# Schematic.net
KiCad netlist of a schematic drawn in EAGLE
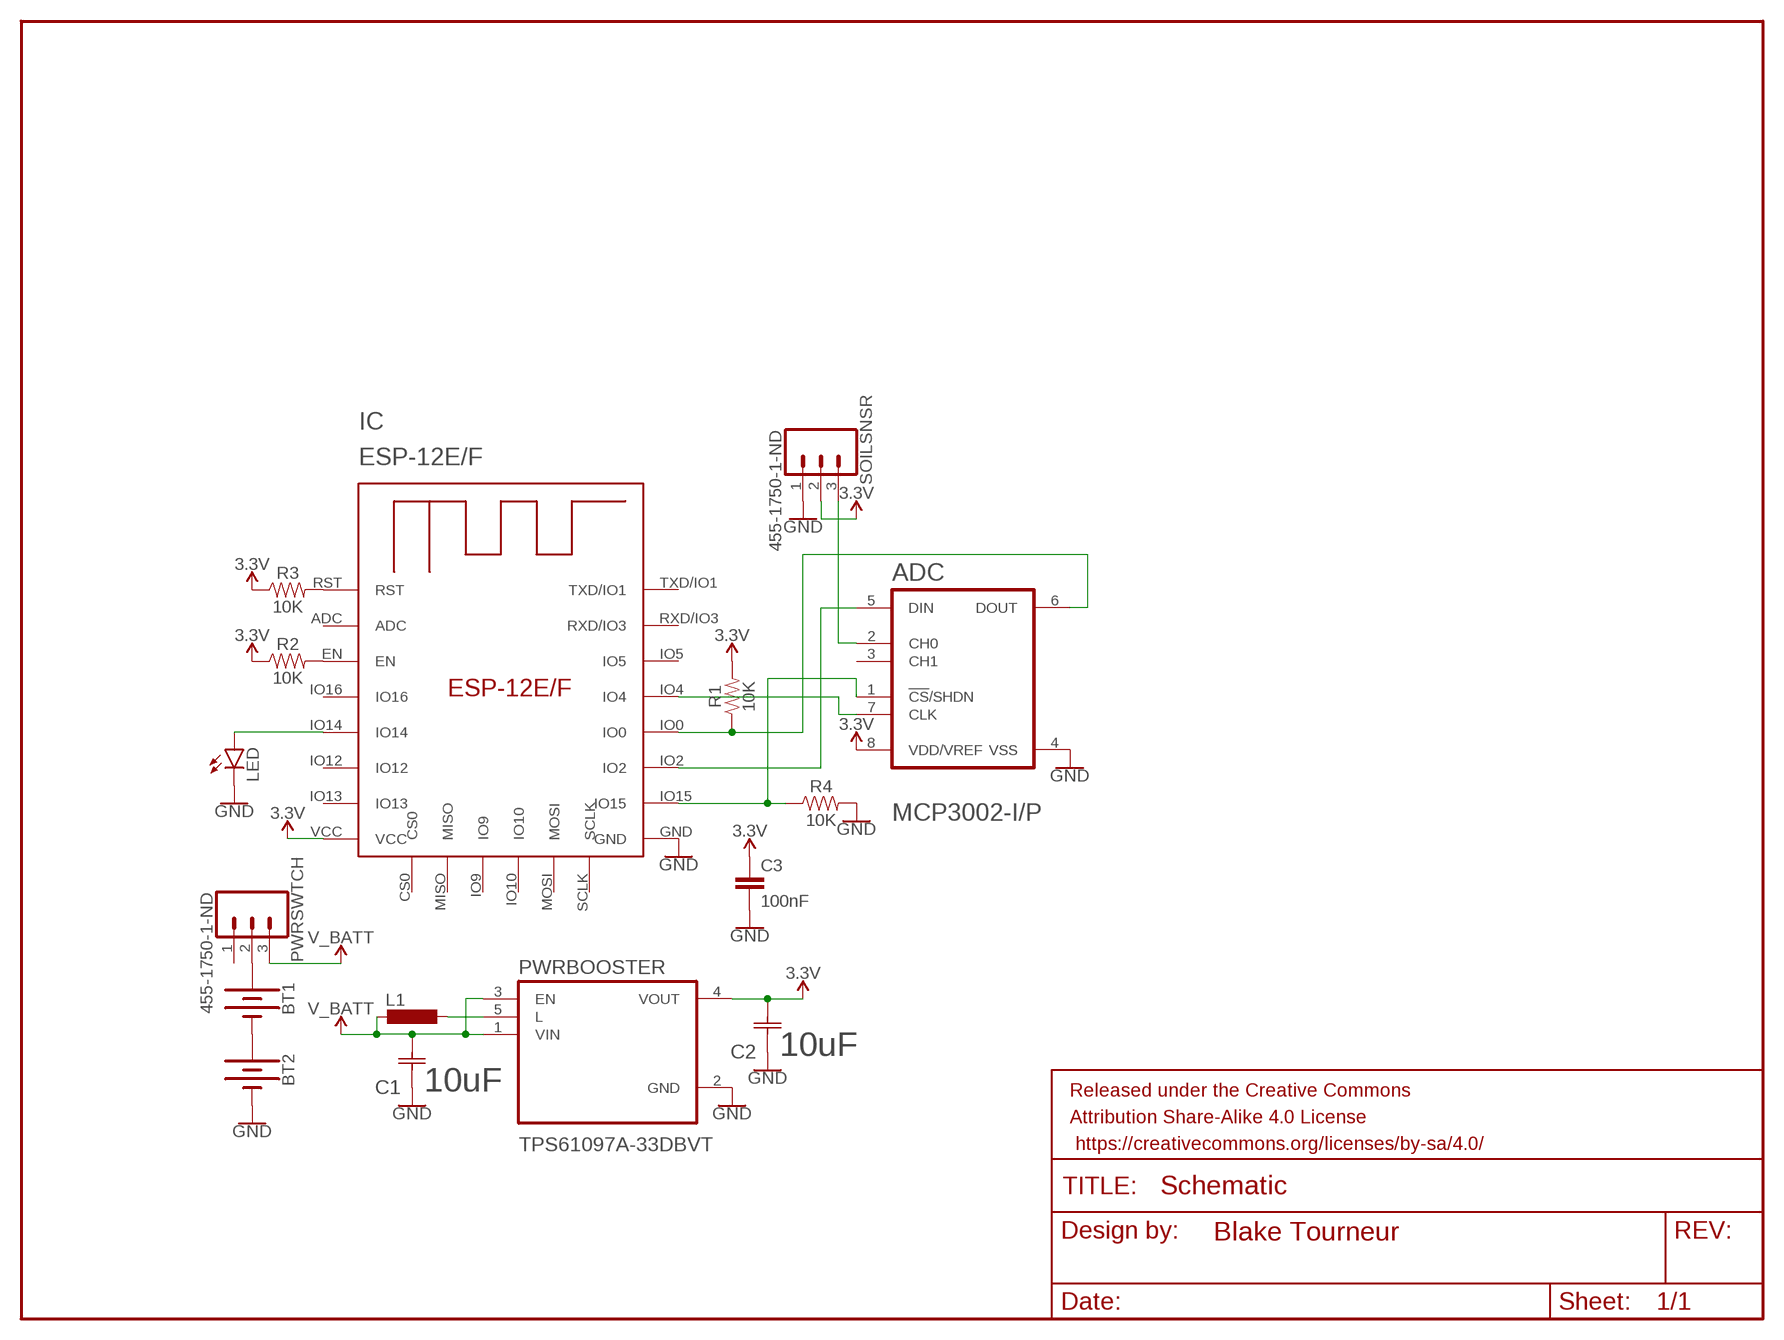
[diagram p0: schematic, sheet 1]

(export (version "E")
  (design (tool "Eeschema 10.0.6"))
  (components
    (comp (ref "ADC")
      (value "MICROCHIP_MCP3002-I-PMICROCHIP_MCP3002-I-P_0_0")
      (footprint "eagle-import:MICROCHIP_MCP3002-I-P_0")
      (fields (field (name "MF") "Microchip") (field (name "MPN") "MCP3002-I/P"))
      (libsource (lib "eagle-import") (part "MICROCHIP_MCP3002-I-PMICROCHIP_MCP3002-I-P_0_0"))
    )
    (comp (ref "BT1")
      (value "BATTERY-AA")
      (footprint "eagle-import:BATTERY-AA")
      (libsource (lib "eagle-import") (part "BATTERY-AA"))
    )
    (comp (ref "BT2")
      (value "BATTERY-AA")
      (footprint "eagle-import:BATTERY-AA")
      (libsource (lib "eagle-import") (part "BATTERY-AA"))
    )
    (comp (ref "C1")
      (value "10uF")
      (footprint "eagle-import:CAPC3216X180N")
      (fields (field (name "MPN") "GRM31CR70J106KA01L") (field (name "TOLERANCE") "±10%"))
      (libsource (lib "eagle-import") (part "GRM31CR70J106KA01L"))
    )
    (comp (ref "C2")
      (value "10uF")
      (footprint "eagle-import:CAPC3216X180N")
      (fields (field (name "MPN") "GRM31CR70J106KA01L") (field (name "TOLERANCE") "±10%"))
      (libsource (lib "eagle-import") (part "GRM31CR70J106KA01L"))
    )
    (comp (ref "C3")
      (value "100nF")
      (footprint "eagle-import:C2.5-3")
      (libsource (lib "eagle-import") (part "C2,5-3"))
    )
    (comp (ref "FRAME1")
      (value "FRAME-LETTERNO_PACKAGE")
      (footprint "eagle-import:DUMMY")
      (fields
        (field (name "DESIGNER") "Blake Tourneur")
        (field (name "DESIGNER_1") "Blake Tourneur")
        (field (name "VERSION") "v02")
      )
      (libsource (lib "eagle-import") (part "FRAME-LETTERNO_PACKAGE"))
    )
    (comp (ref "IC")
      (value "ESP-12E/F")
      (footprint "eagle-import:ESP-12E")
      (libsource (lib "eagle-import") (part "ESP-12E/F"))
    )
    (comp (ref "L1")
      (value "DO3316P")
      (footprint "eagle-import:DO3316P")
      (libsource (lib "eagle-import") (part "DO3316P"))
    )
    (comp (ref "LED")
      (value "LED3MM")
      (footprint "eagle-import:LED3MM")
      (libsource (lib "eagle-import") (part "LED3MM"))
    )
    (comp (ref "PWRBOOSTER")
      (value "TPS61097A-33DBVT")
      (footprint "eagle-import:SOT95P280X145-5N")
      (fields (field (name "MF") "Texas Instruments"))
      (libsource (lib "eagle-import") (part "TPS61097A-33DBVT"))
    )
    (comp (ref "PWRSWTCH")
      (value "455-1750-1-ND")
      (footprint "eagle-import:1X03")
      (libsource (lib "eagle-import") (part "CONN_03"))
    )
    (comp (ref "R1")
      (value "10K")
      (footprint "eagle-import:0402-TIGHT")
      (libsource (lib "eagle-import") (part "10KOHM-0402-1/10W-0.1%"))
    )
    (comp (ref "R2")
      (value "10K")
      (footprint "eagle-import:0402-TIGHT")
      (libsource (lib "eagle-import") (part "10KOHM-0402-1/10W-0.1%"))
    )
    (comp (ref "R3")
      (value "10K")
      (footprint "eagle-import:0402-TIGHT")
      (libsource (lib "eagle-import") (part "10KOHM-0402-1/10W-0.1%"))
    )
    (comp (ref "R4")
      (value "10K")
      (footprint "eagle-import:0402-TIGHT")
      (libsource (lib "eagle-import") (part "10KOHM-0402-1/10W-0.1%"))
    )
    (comp (ref "SOILSNSR")
      (value "455-1750-1-ND")
      (footprint "eagle-import:1X03")
      (libsource (lib "eagle-import") (part "CONN_03"))
    )
  )
  (nets
    (net (code "1") (name "3.3V") (class "Default")
      (node (ref "ADC") (pin "8") (pinfunction "VDD/VREF_8") (pintype "power_in"))
      (node (ref "C2") (pin "2") (pinfunction "C2_2") (pintype "passive"))
      (node (ref "C3") (pin "1") (pinfunction "1_1") (pintype "passive"))
      (node (ref "IC") (pin "VCC") (pinfunction "VCC_VCC") (pintype "power_in"))
      (node (ref "PWRBOOSTER") (pin "4") (pinfunction "VOUT_4") (pintype "output"))
      (node (ref "R1") (pin "2") (pinfunction "2_2") (pintype "passive"))
      (node (ref "R2") (pin "1") (pinfunction "1_1") (pintype "passive"))
      (node (ref "R3") (pin "1") (pinfunction "1_1") (pintype "passive"))
      (node (ref "SOILSNSR") (pin "2") (pinfunction "2_2") (pintype "passive"))
    )
    (net (code "2") (name "GND") (class "Default")
      (node (ref "ADC") (pin "4") (pinfunction "VSS_4") (pintype "power_in"))
      (node (ref "BT2") (pin "GND@1") (pinfunction "-_GND@1") (pintype "power_in"))
      (node (ref "C1") (pin "1") (pinfunction "C1_1") (pintype "passive"))
      (node (ref "C2") (pin "1") (pinfunction "C1_1") (pintype "passive"))
      (node (ref "C3") (pin "2") (pinfunction "2_2") (pintype "passive"))
      (node (ref "IC") (pin "GND") (pinfunction "GND_GND") (pintype "power_in"))
      (node (ref "LED") (pin "K") (pinfunction "C_K") (pintype "passive"))
      (node (ref "PWRBOOSTER") (pin "2") (pinfunction "GND_2") (pintype "power_in"))
      (node (ref "R4") (pin "2") (pinfunction "2_2") (pintype "passive"))
      (node (ref "SOILSNSR") (pin "1") (pinfunction "1_1") (pintype "passive"))
    )
    (net (code "3") (name "Net-(ADC-CH0)") (class "Default")
      (node (ref "ADC") (pin "2") (pinfunction "CH0_2") (pintype "input"))
      (node (ref "SOILSNSR") (pin "3") (pinfunction "3_3") (pintype "passive"))
    )
    (net (code "4") (name "Net-(ADC-CLK)") (class "Default")
      (node (ref "ADC") (pin "7") (pinfunction "CLK_7") (pintype "input"))
      (node (ref "IC") (pin "IO4") (pinfunction "IO4_IO4") (pintype "bidirectional"))
    )
    (net (code "5") (name "Net-(ADC-DIN)") (class "Default")
      (node (ref "ADC") (pin "5") (pinfunction "DIN_5") (pintype "input"))
      (node (ref "IC") (pin "IO2") (pinfunction "IO2_IO2") (pintype "bidirectional"))
    )
    (net (code "6") (name "Net-(ADC-DOUT)") (class "Default")
      (node (ref "ADC") (pin "6") (pinfunction "DOUT_6") (pintype "tri_state"))
      (node (ref "IC") (pin "IO0") (pinfunction "IO0_IO0") (pintype "bidirectional"))
      (node (ref "R1") (pin "1") (pinfunction "1_1") (pintype "passive"))
    )
    (net (code "7") (name "Net-(ADC-~{CS}{slash}SHDN)") (class "Default")
      (node (ref "ADC") (pin "1") (pinfunction "~{CS}/SHDN_1") (pintype "input"))
      (node (ref "IC") (pin "IO15") (pinfunction "IO15_IO15") (pintype "bidirectional"))
      (node (ref "R4") (pin "1") (pinfunction "1_1") (pintype "passive"))
    )
    (net (code "8") (name "Net-(BT1-+)") (class "Default")
      (node (ref "BT1") (pin "PWR@1") (pinfunction "+_PWR@1") (pintype "power_in"))
      (node (ref "PWRSWTCH") (pin "2") (pinfunction "2_2") (pintype "passive"))
    )
    (net (code "9") (name "Net-(BT1--)") (class "Default")
      (node (ref "BT1") (pin "GND@1") (pinfunction "-_GND@1") (pintype "power_in"))
      (node (ref "BT2") (pin "PWR@1") (pinfunction "+_PWR@1") (pintype "power_in"))
    )
    (net (code "10") (name "Net-(IC-PadEN)") (class "Default")
      (node (ref "IC") (pin "EN") (pinfunction "EN_EN") (pintype "bidirectional"))
      (node (ref "R2") (pin "2") (pinfunction "2_2") (pintype "passive"))
    )
    (net (code "11") (name "Net-(IC-PadIO14)") (class "Default")
      (node (ref "IC") (pin "IO14") (pinfunction "IO14_IO14") (pintype "bidirectional"))
      (node (ref "LED") (pin "A") (pinfunction "A_A") (pintype "passive"))
    )
    (net (code "12") (name "Net-(IC-PadRST)") (class "Default")
      (node (ref "IC") (pin "RST") (pinfunction "RST_RST") (pintype "input"))
      (node (ref "R3") (pin "2") (pinfunction "2_2") (pintype "passive"))
    )
    (net (code "13") (name "Net-(PWRBOOSTER-L)") (class "Default")
      (node (ref "L1") (pin "2") (pinfunction "2_2") (pintype "passive"))
      (node (ref "PWRBOOSTER") (pin "5") (pinfunction "L_5") (pintype "input"))
    )
    (net (code "14") (name "V_BATT") (class "Default")
      (node (ref "C1") (pin "2") (pinfunction "C2_2") (pintype "passive"))
      (node (ref "L1") (pin "1") (pinfunction "1_1") (pintype "passive"))
      (node (ref "PWRBOOSTER") (pin "1") (pinfunction "VIN_1") (pintype "input"))
      (node (ref "PWRBOOSTER") (pin "3") (pinfunction "EN_3") (pintype "input"))
      (node (ref "PWRSWTCH") (pin "3") (pinfunction "3_3") (pintype "passive"))
    )
    (net (code "15") (name "unconnected-(ADC-CH1-Pad3)") (class "Default")
      (node (ref "ADC") (pin "3") (pinfunction "CH1_3") (pintype "input"))
    )
    (net (code "16") (name "unconnected-(IC-PadADC)") (class "Default")
      (node (ref "IC") (pin "ADC") (pinfunction "ADC_ADC") (pintype "bidirectional"))
    )
    (net (code "17") (name "unconnected-(IC-PadCS0)") (class "Default")
      (node (ref "IC") (pin "CS0") (pinfunction "CS0_CS0") (pintype "bidirectional"))
    )
    (net (code "18") (name "unconnected-(IC-PadIO5)") (class "Default")
      (node (ref "IC") (pin "IO5") (pinfunction "IO5_IO5") (pintype "bidirectional"))
    )
    (net (code "19") (name "unconnected-(IC-PadIO9)") (class "Default")
      (node (ref "IC") (pin "IO9") (pinfunction "IO9_IO9") (pintype "bidirectional"))
    )
    (net (code "20") (name "unconnected-(IC-PadIO10)") (class "Default")
      (node (ref "IC") (pin "IO10") (pinfunction "IO10_IO10") (pintype "bidirectional"))
    )
    (net (code "21") (name "unconnected-(IC-PadIO12)") (class "Default")
      (node (ref "IC") (pin "IO12") (pinfunction "IO12_IO12") (pintype "bidirectional"))
    )
    (net (code "22") (name "unconnected-(IC-PadIO13)") (class "Default")
      (node (ref "IC") (pin "IO13") (pinfunction "IO13_IO13") (pintype "bidirectional"))
    )
    (net (code "23") (name "unconnected-(IC-PadIO16)") (class "Default")
      (node (ref "IC") (pin "IO16") (pinfunction "IO16_IO16") (pintype "bidirectional"))
    )
    (net (code "24") (name "unconnected-(IC-PadMISO)") (class "Default")
      (node (ref "IC") (pin "MISO") (pinfunction "MISO_MISO") (pintype "bidirectional"))
    )
    (net (code "25") (name "unconnected-(IC-PadMOSI)") (class "Default")
      (node (ref "IC") (pin "MOSI") (pinfunction "MOSI_MOSI") (pintype "bidirectional"))
    )
    (net (code "26") (name "unconnected-(IC-PadRXD{slash}IO3)") (class "Default")
      (node (ref "IC") (pin "RXD/IO3") (pinfunction "RXD/IO3_RXD/IO3") (pintype "bidirectional"))
    )
    (net (code "27") (name "unconnected-(IC-PadSCLK)") (class "Default")
      (node (ref "IC") (pin "SCLK") (pinfunction "SCLK_SCLK") (pintype "bidirectional"))
    )
    (net (code "28") (name "unconnected-(IC-PadTXD{slash}IO1)") (class "Default")
      (node (ref "IC") (pin "TXD/IO1") (pinfunction "TXD/IO1_TXD/IO1") (pintype "bidirectional"))
    )
    (net (code "29") (name "unconnected-(PWRSWTCH-Pad1)") (class "Default")
      (node (ref "PWRSWTCH") (pin "1") (pinfunction "1_1") (pintype "passive"))
    )
  )
)
